# 09_TFCARD_USB2_0.net
KiCad netlist of a schematic drawn in Altium Designer
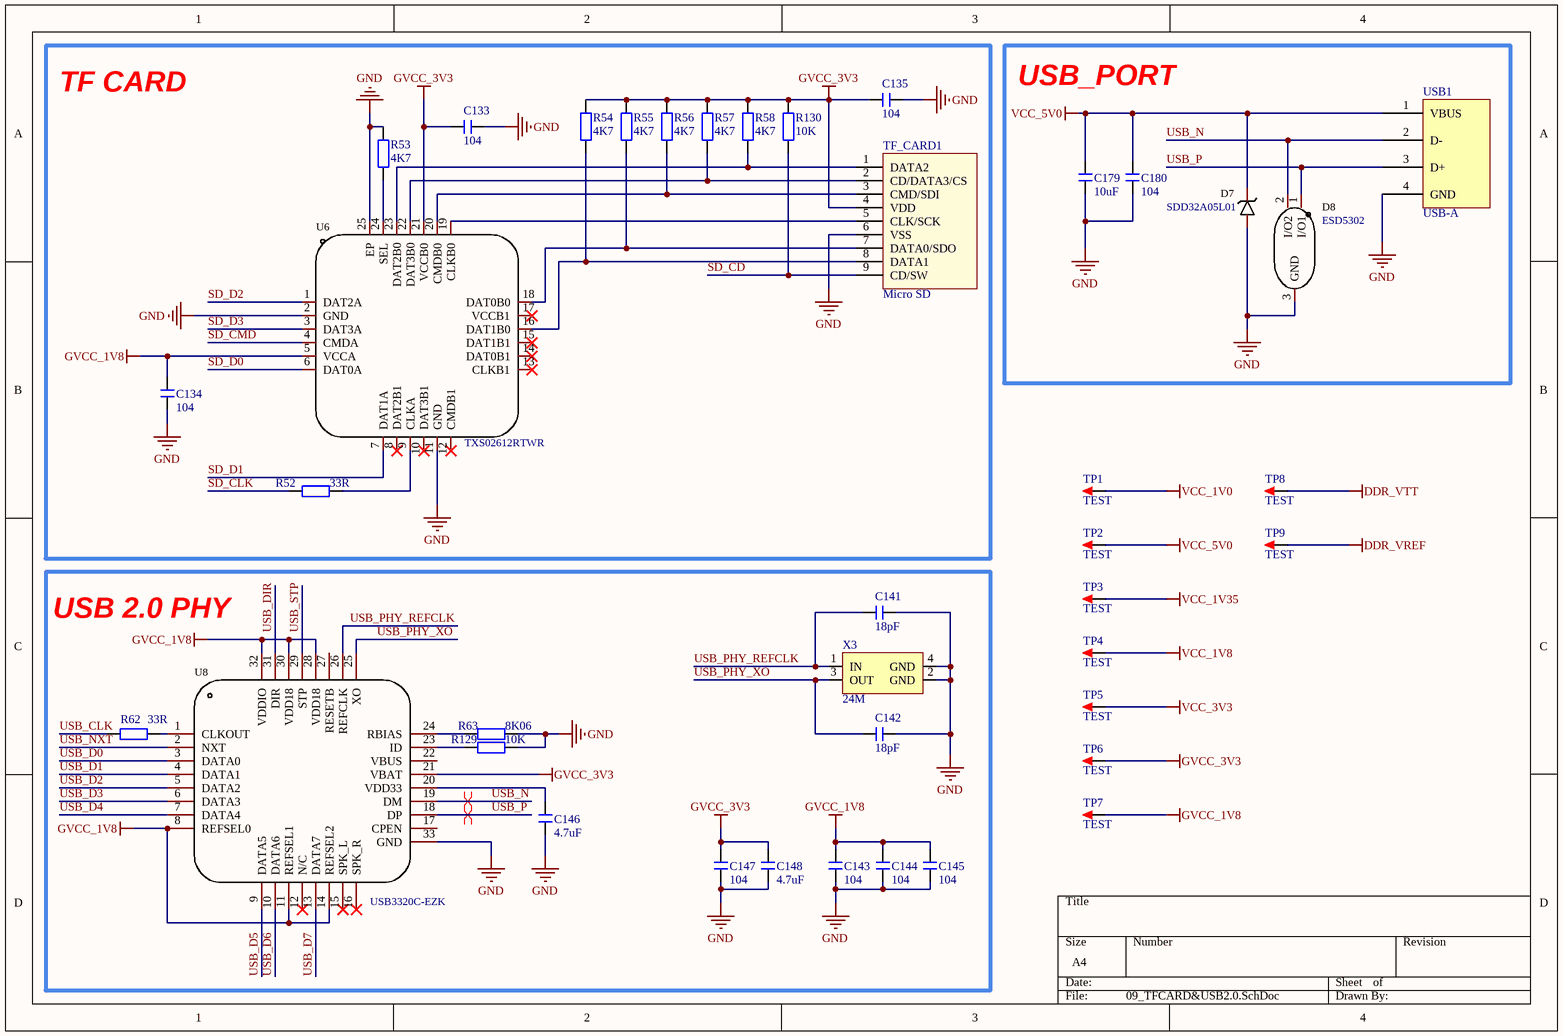
[diagram p0: 09_TFCARD&USB2.0.SchDoc]

(export (version "E")
  (design (tool "Eeschema 10.0.6"))
  (components
    (comp (ref "C133")
      (value "104")
      (footprint "C 0603")
      (description "无极性贴片电容")
      (fields (field (name "版权归属") "源创客"))
      (libsource (lib "STM32MP15x底板封装库V1.4") (part "C"))
    )
    (comp (ref "C134")
      (value "104")
      (footprint "C 0603")
      (description "无极性贴片电容")
      (fields (field (name "版权归属") "源创客"))
      (libsource (lib "STM32MP15x底板封装库V1.4") (part "C"))
    )
    (comp (ref "C135")
      (value "104")
      (footprint "C 0603")
      (description "无极性贴片电容")
      (fields (field (name "版权归属") "源创客"))
      (libsource (lib "STM32MP15x底板封装库V1.4") (part "C"))
    )
    (comp (ref "C141")
      (value "18pF")
      (footprint "C 0603")
      (description "无极性贴片电容")
      (fields (field (name "版权归属") "源创客"))
      (libsource (lib "STM32MP15x底板封装库V1.4") (part "C"))
    )
    (comp (ref "C142")
      (value "18pF")
      (footprint "C 0603")
      (description "无极性贴片电容")
      (fields (field (name "版权归属") "源创客"))
      (libsource (lib "STM32MP15x底板封装库V1.4") (part "C"))
    )
    (comp (ref "C143")
      (value "104")
      (footprint "C 0603")
      (description "无极性贴片电容")
      (fields (field (name "版权归属") "源创客"))
      (libsource (lib "STM32MP15x底板封装库V1.4") (part "C"))
    )
    (comp (ref "C144")
      (value "104")
      (footprint "C 0603")
      (description "无极性贴片电容")
      (fields (field (name "版权归属") "源创客"))
      (libsource (lib "STM32MP15x底板封装库V1.4") (part "C"))
    )
    (comp (ref "C145")
      (value "104")
      (footprint "C 0603")
      (description "无极性贴片电容")
      (fields (field (name "版权归属") "源创客"))
      (libsource (lib "STM32MP15x底板封装库V1.4") (part "C"))
    )
    (comp (ref "C146")
      (value "4.7uF")
      (footprint "C 0603")
      (description "无极性贴片电容")
      (fields (field (name "版权归属") "源创客"))
      (libsource (lib "STM32MP15x底板封装库V1.4") (part "C"))
    )
    (comp (ref "C147")
      (value "104")
      (footprint "C 0603")
      (description "无极性贴片电容")
      (fields (field (name "版权归属") "源创客"))
      (libsource (lib "STM32MP15x底板封装库V1.4") (part "C"))
    )
    (comp (ref "C148")
      (value "4.7uF")
      (footprint "C 0603")
      (description "无极性贴片电容")
      (fields (field (name "版权归属") "源创客"))
      (libsource (lib "STM32MP15x底板封装库V1.4") (part "C"))
    )
    (comp (ref "C179")
      (value "10uF")
      (footprint "C 0805")
      (description "无极性贴片电容")
      (fields (field (name "版权归属") "源创客"))
      (libsource (lib "STM32MP15x底板封装库V1.4") (part "C"))
    )
    (comp (ref "C180")
      (value "104")
      (footprint "C 0603")
      (description "无极性贴片电容")
      (fields (field (name "版权归属") "源创客"))
      (libsource (lib "STM32MP15x底板封装库V1.4") (part "C"))
    )
    (comp (ref "D7")
      (value "SDD32A05L01")
      (footprint "SOD-323")
      (fields (field (name "MANUFACTURER") "Brightking(君耀电子)"))
      (libsource (lib "SDD32A05L01") (part "SDD32A05L01"))
    )
    (comp (ref "D8")
      (value "ESD5302")
      (footprint "SOT23-3M")
      (fields (field (name "MANUFACTURER") "MSKSEMI(美森科)") (field (name "MANUFACTURER PART") "ESD5302F-MS"))
      (libsource (lib "ESD5302") (part "ESD5302"))
    )
    (comp (ref "R52")
      (value "33R")
      (footprint "R 0603")
      (description "贴片电阻")
      (fields (field (name "版权归属") "源创客"))
      (libsource (lib "STM32MP15x底板封装库V1.4") (part "R"))
    )
    (comp (ref "R53")
      (value "4K7")
      (footprint "R 0603")
      (description "贴片电阻")
      (fields (field (name "版权归属") "源创客"))
      (libsource (lib "STM32MP15x底板封装库V1.4") (part "R"))
    )
    (comp (ref "R54")
      (value "4K7")
      (footprint "R 0603")
      (description "贴片电阻")
      (fields (field (name "版权归属") "源创客"))
      (libsource (lib "STM32MP15x底板封装库V1.4") (part "R"))
    )
    (comp (ref "R55")
      (value "4K7")
      (footprint "R 0603")
      (description "贴片电阻")
      (fields (field (name "版权归属") "源创客"))
      (libsource (lib "STM32MP15x底板封装库V1.4") (part "R"))
    )
    (comp (ref "R56")
      (value "4K7")
      (footprint "R 0603")
      (description "贴片电阻")
      (fields (field (name "版权归属") "源创客"))
      (libsource (lib "STM32MP15x底板封装库V1.4") (part "R"))
    )
    (comp (ref "R57")
      (value "4K7")
      (footprint "R 0603")
      (description "贴片电阻")
      (fields (field (name "版权归属") "源创客"))
      (libsource (lib "STM32MP15x底板封装库V1.4") (part "R"))
    )
    (comp (ref "R58")
      (value "4K7")
      (footprint "R 0603")
      (description "贴片电阻")
      (fields (field (name "版权归属") "源创客"))
      (libsource (lib "STM32MP15x底板封装库V1.4") (part "R"))
    )
    (comp (ref "R62")
      (value "33R")
      (footprint "R 0603")
      (description "贴片电阻")
      (fields (field (name "版权归属") "源创客"))
      (libsource (lib "STM32MP15x底板封装库V1.4") (part "R"))
    )
    (comp (ref "R63")
      (value "8K06")
      (footprint "R 0603")
      (description "贴片电阻")
      (fields (field (name "版权归属") "源创客"))
      (libsource (lib "STM32MP15x底板封装库V1.4") (part "R"))
    )
    (comp (ref "R129")
      (value "10K")
      (footprint "R 0603")
      (description "贴片电阻")
      (fields (field (name "版权归属") "源创客"))
      (libsource (lib "STM32MP15x底板封装库V1.4") (part "R"))
    )
    (comp (ref "R130")
      (value "10K")
      (footprint "R 0603")
      (description "贴片电阻")
      (fields (field (name "版权归属") "源创客"))
      (libsource (lib "STM32MP15x底板封装库V1.4") (part "R"))
    )
    (comp (ref "TF_CARD1")
      (value "Micro SD")
      (footprint "Micro SD")
      (description "Micro SD卡")
      (fields (field (name "版权归属") "源创客"))
      (libsource (lib "STM32MP15x底板封装库V1.4") (part "Micro SD"))
    )
    (comp (ref "TP1")
      (value "TEST")
      (footprint "TEST 1")
      (description "测试点")
      (fields (field (name "版权归属") "源创客"))
      (libsource (lib "15.1 - 未分类器件") (part "TEST"))
    )
    (comp (ref "TP2")
      (value "TEST")
      (footprint "TEST 1")
      (description "测试点")
      (fields (field (name "版权归属") "源创客"))
      (libsource (lib "15.1 - 未分类器件") (part "TEST"))
    )
    (comp (ref "TP3")
      (value "TEST")
      (footprint "TEST 1")
      (description "测试点")
      (fields (field (name "版权归属") "源创客"))
      (libsource (lib "15.1 - 未分类器件") (part "TEST"))
    )
    (comp (ref "TP4")
      (value "TEST")
      (footprint "TEST 1")
      (description "测试点")
      (fields (field (name "版权归属") "源创客"))
      (libsource (lib "15.1 - 未分类器件") (part "TEST"))
    )
    (comp (ref "TP5")
      (value "TEST")
      (footprint "TEST 1")
      (description "测试点")
      (fields (field (name "版权归属") "源创客"))
      (libsource (lib "15.1 - 未分类器件") (part "TEST"))
    )
    (comp (ref "TP6")
      (value "TEST")
      (footprint "TEST 1")
      (description "测试点")
      (fields (field (name "版权归属") "源创客"))
      (libsource (lib "15.1 - 未分类器件") (part "TEST"))
    )
    (comp (ref "TP7")
      (value "TEST")
      (footprint "TEST 1")
      (description "测试点")
      (fields (field (name "版权归属") "源创客"))
      (libsource (lib "15.1 - 未分类器件") (part "TEST"))
    )
    (comp (ref "TP8")
      (value "TEST")
      (footprint "TEST 1")
      (description "测试点")
      (fields (field (name "版权归属") "源创客"))
      (libsource (lib "15.1 - 未分类器件") (part "TEST"))
    )
    (comp (ref "TP9")
      (value "TEST")
      (footprint "TEST 1")
      (description "测试点")
      (fields (field (name "版权归属") "源创客"))
      (libsource (lib "15.1 - 未分类器件") (part "TEST"))
    )
    (comp (ref "U6")
      (value "TXS02612RTWR")
      (footprint "QFN24 4x4_N")
      (fields (field (name "MANUFACTURER") "TI(德州仪器)"))
      (libsource (lib "TXS02612RTWR") (part "TXS02612RTWR"))
    )
    (comp (ref "U8")
      (value "USB3320C-EZK")
      (footprint "QFN32 5x5_L")
      (fields (field (name "MANUFACTURER") "MICROCHIP(美国微芯)"))
      (libsource (lib "USB3320C-EZK1") (part "USB3320C-EZK"))
    )
    (comp (ref "USB1") (value "USB-A") (footprint "USB-Short") (libsource (lib "Atom-N") (part "USB-A")))
    (comp (ref "X3")
      (value "24M")
      (footprint "XTAL-3225")
      (description "4脚无源晶振")
      (fields (field (name "版权归属") "源创客"))
      (libsource (lib "STM32MP15x底板封装库V1.4") (part "XTAL-4P"))
    )
  )
  (nets
    (net (code "1") (name "/SD_CD") (class "Default")
      (node (ref "R130") (pin "1") (pinfunction "1_1") (pintype "passive"))
      (node (ref "TF_CARD1") (pin "9") (pinfunction "CD/SW_9") (pintype "passive"))
    )
    (net (code "2") (name "/SD_CLK") (class "Default")
      (node (ref "R52") (pin "1") (pinfunction "1_1") (pintype "passive"))
    )
    (net (code "3") (name "/SD_CMD") (class "Default")
      (node (ref "U6") (pin "4") (pinfunction "CMDA_4") (pintype "passive"))
    )
    (net (code "4") (name "/SD_D0") (class "Default")
      (node (ref "U6") (pin "6") (pinfunction "DAT0A_6") (pintype "passive"))
    )
    (net (code "5") (name "/SD_D1") (class "Default")
      (node (ref "U6") (pin "7") (pinfunction "DAT1A_7") (pintype "passive"))
    )
    (net (code "6") (name "/SD_D2") (class "Default")
      (node (ref "U6") (pin "1") (pinfunction "DAT2A_1") (pintype "passive"))
    )
    (net (code "7") (name "/SD_D3") (class "Default")
      (node (ref "U6") (pin "3") (pinfunction "DAT3A_3") (pintype "passive"))
    )
    (net (code "8") (name "/USB_CLK") (class "Default")
      (node (ref "R62") (pin "2") (pinfunction "2_2") (pintype "passive"))
    )
    (net (code "9") (name "/USB_D0") (class "Default")
      (node (ref "U8") (pin "3") (pinfunction "DATA0_3") (pintype "passive"))
    )
    (net (code "10") (name "/USB_D1") (class "Default")
      (node (ref "U8") (pin "4") (pinfunction "DATA1_4") (pintype "passive"))
    )
    (net (code "11") (name "/USB_D2") (class "Default")
      (node (ref "U8") (pin "5") (pinfunction "DATA2_5") (pintype "passive"))
    )
    (net (code "12") (name "/USB_D3") (class "Default")
      (node (ref "U8") (pin "6") (pinfunction "DATA3_6") (pintype "passive"))
    )
    (net (code "13") (name "/USB_D4") (class "Default")
      (node (ref "U8") (pin "7") (pinfunction "DATA4_7") (pintype "passive"))
    )
    (net (code "14") (name "/USB_D5") (class "Default")
      (node (ref "U8") (pin "9") (pinfunction "DATA5_9") (pintype "passive"))
    )
    (net (code "15") (name "/USB_D6") (class "Default")
      (node (ref "U8") (pin "10") (pinfunction "DATA6_10") (pintype "passive"))
    )
    (net (code "16") (name "/USB_D7") (class "Default")
      (node (ref "U8") (pin "13") (pinfunction "DATA7_13") (pintype "passive"))
    )
    (net (code "17") (name "/USB_DIR") (class "Default")
      (node (ref "U8") (pin "31") (pinfunction "DIR_31") (pintype "passive"))
    )
    (net (code "18") (name "/USB_N") (class "Default")
      (node (ref "D8") (pin "2") (pinfunction "I/O2_2") (pintype "passive"))
      (node (ref "U8") (pin "19") (pinfunction "DM_19") (pintype "passive"))
      (node (ref "USB1") (pin "2") (pinfunction "D-_2") (pintype "passive"))
    )
    (net (code "19") (name "/USB_NXT") (class "Default")
      (node (ref "U8") (pin "2") (pinfunction "NXT_2") (pintype "passive"))
    )
    (net (code "20") (name "/USB_P") (class "Default")
      (node (ref "D8") (pin "1") (pinfunction "I/O1_1") (pintype "passive"))
      (node (ref "U8") (pin "18") (pinfunction "DP_18") (pintype "passive"))
      (node (ref "USB1") (pin "3") (pinfunction "D+_3") (pintype "passive"))
    )
    (net (code "21") (name "/USB_PHY_REFCLK") (class "Default")
      (node (ref "C141") (pin "2") (pinfunction "2_2") (pintype "passive"))
      (node (ref "U8") (pin "26") (pinfunction "REFCLK_26") (pintype "passive"))
      (node (ref "X3") (pin "1") (pinfunction "IN_1") (pintype "passive"))
    )
    (net (code "22") (name "/USB_PHY_XO") (class "Default")
      (node (ref "C142") (pin "2") (pinfunction "2_2") (pintype "passive"))
      (node (ref "U8") (pin "25") (pinfunction "XO_25") (pintype "passive"))
      (node (ref "X3") (pin "3") (pinfunction "OUT_3") (pintype "passive"))
    )
    (net (code "23") (name "/USB_STP") (class "Default")
      (node (ref "U8") (pin "29") (pinfunction "STP_29") (pintype "passive"))
    )
    (net (code "24") (name "DDR_VREF") (class "Default")
      (node (ref "TP9") (pin "1") (pinfunction "1_1") (pintype "passive"))
    )
    (net (code "25") (name "DDR_VTT") (class "Default")
      (node (ref "TP8") (pin "1") (pinfunction "1_1") (pintype "passive"))
    )
    (net (code "26") (name "GND") (class "Default")
      (node (ref "C133") (pin "1") (pinfunction "1_1") (pintype "passive"))
      (node (ref "C134") (pin "1") (pinfunction "1_1") (pintype "passive"))
      (node (ref "C135") (pin "2") (pinfunction "2_2") (pintype "passive"))
      (node (ref "C141") (pin "1") (pinfunction "1_1") (pintype "passive"))
      (node (ref "C142") (pin "1") (pinfunction "1_1") (pintype "passive"))
      (node (ref "C143") (pin "1") (pinfunction "1_1") (pintype "passive"))
      (node (ref "C144") (pin "1") (pinfunction "1_1") (pintype "passive"))
      (node (ref "C145") (pin "1") (pinfunction "1_1") (pintype "passive"))
      (node (ref "C146") (pin "1") (pinfunction "1_1") (pintype "passive"))
      (node (ref "C147") (pin "1") (pinfunction "1_1") (pintype "passive"))
      (node (ref "C148") (pin "1") (pinfunction "1_1") (pintype "passive"))
      (node (ref "C179") (pin "1") (pinfunction "1_1") (pintype "passive"))
      (node (ref "C180") (pin "1") (pinfunction "1_1") (pintype "passive"))
      (node (ref "D7") (pin "2") (pinfunction "A_2") (pintype "passive"))
      (node (ref "D8") (pin "3") (pinfunction "GND_3") (pintype "passive"))
      (node (ref "R129") (pin "2") (pinfunction "2_2") (pintype "passive"))
      (node (ref "R53") (pin "2") (pinfunction "2_2") (pintype "passive"))
      (node (ref "R63") (pin "2") (pinfunction "2_2") (pintype "passive"))
      (node (ref "TF_CARD1") (pin "6") (pinfunction "VSS_6") (pintype "passive"))
      (node (ref "U6") (pin "11") (pinfunction "GND_11") (pintype "passive"))
      (node (ref "U6") (pin "2") (pinfunction "GND_2") (pintype "passive"))
      (node (ref "U6") (pin "25") (pinfunction "EP_25") (pintype "passive"))
      (node (ref "U8") (pin "33") (pinfunction "GND_33") (pintype "passive"))
      (node (ref "USB1") (pin "4") (pinfunction "GND_4") (pintype "passive"))
      (node (ref "X3") (pin "2") (pinfunction "GND_2") (pintype "passive"))
      (node (ref "X3") (pin "4") (pinfunction "GND_4") (pintype "passive"))
    )
    (net (code "27") (name "GVCC_1V8") (class "Default")
      (node (ref "C134") (pin "2") (pinfunction "2_2") (pintype "passive"))
      (node (ref "C143") (pin "2") (pinfunction "2_2") (pintype "passive"))
      (node (ref "C144") (pin "2") (pinfunction "2_2") (pintype "passive"))
      (node (ref "C145") (pin "2") (pinfunction "2_2") (pintype "passive"))
      (node (ref "TP7") (pin "1") (pinfunction "1_1") (pintype "passive"))
      (node (ref "U6") (pin "5") (pinfunction "VCCA_5") (pintype "passive"))
      (node (ref "U8") (pin "11") (pinfunction "REFSEL1_11") (pintype "passive"))
      (node (ref "U8") (pin "14") (pinfunction "REFSEL2_14") (pintype "passive"))
      (node (ref "U8") (pin "28") (pinfunction "VDD18_28") (pintype "passive"))
      (node (ref "U8") (pin "30") (pinfunction "VDD18_30") (pintype "passive"))
      (node (ref "U8") (pin "32") (pinfunction "VDDIO_32") (pintype "passive"))
      (node (ref "U8") (pin "8") (pinfunction "REFSEL0_8") (pintype "passive"))
    )
    (net (code "28") (name "GVCC_3V3") (class "Default")
      (node (ref "C133") (pin "2") (pinfunction "2_2") (pintype "passive"))
      (node (ref "C135") (pin "1") (pinfunction "1_1") (pintype "passive"))
      (node (ref "C147") (pin "2") (pinfunction "2_2") (pintype "passive"))
      (node (ref "C148") (pin "2") (pinfunction "2_2") (pintype "passive"))
      (node (ref "R130") (pin "2") (pinfunction "2_2") (pintype "passive"))
      (node (ref "R54") (pin "2") (pinfunction "2_2") (pintype "passive"))
      (node (ref "R55") (pin "2") (pinfunction "2_2") (pintype "passive"))
      (node (ref "R56") (pin "2") (pinfunction "2_2") (pintype "passive"))
      (node (ref "R57") (pin "2") (pinfunction "2_2") (pintype "passive"))
      (node (ref "R58") (pin "2") (pinfunction "2_2") (pintype "passive"))
      (node (ref "TF_CARD1") (pin "4") (pinfunction "VDD_4") (pintype "passive"))
      (node (ref "TP6") (pin "1") (pinfunction "1_1") (pintype "passive"))
      (node (ref "U6") (pin "21") (pinfunction "VCCB0_21") (pintype "passive"))
      (node (ref "U8") (pin "21") (pinfunction "VBAT_21") (pintype "passive"))
    )
    (net (code "29") (name "Net-(TF_CARD1-CD{slash}DATA3{slash}CS)") (class "Default")
      (node (ref "R57") (pin "1") (pinfunction "1_1") (pintype "passive"))
      (node (ref "TF_CARD1") (pin "2") (pinfunction "CD/DATA3/CS_2") (pintype "passive"))
      (node (ref "U6") (pin "22") (pinfunction "DAT3B0_22") (pintype "passive"))
    )
    (net (code "30") (name "Net-(TF_CARD1-CLK{slash}SCK)") (class "Default")
      (node (ref "TF_CARD1") (pin "5") (pinfunction "CLK/SCK_5") (pintype "passive"))
      (node (ref "U6") (pin "19") (pinfunction "CLKB0_19") (pintype "passive"))
    )
    (net (code "31") (name "Net-(TF_CARD1-CMD{slash}SDI)") (class "Default")
      (node (ref "R56") (pin "1") (pinfunction "1_1") (pintype "passive"))
      (node (ref "TF_CARD1") (pin "3") (pinfunction "CMD/SDI_3") (pintype "passive"))
      (node (ref "U6") (pin "20") (pinfunction "CMDB0_20") (pintype "passive"))
    )
    (net (code "32") (name "Net-(TF_CARD1-DATA0{slash}SDO)") (class "Default")
      (node (ref "R55") (pin "1") (pinfunction "1_1") (pintype "passive"))
      (node (ref "TF_CARD1") (pin "7") (pinfunction "DATA0/SDO_7") (pintype "passive"))
      (node (ref "U6") (pin "18") (pinfunction "DAT0B0_18") (pintype "passive"))
    )
    (net (code "33") (name "Net-(TF_CARD1-DATA1)") (class "Default")
      (node (ref "R54") (pin "1") (pinfunction "1_1") (pintype "passive"))
      (node (ref "TF_CARD1") (pin "8") (pinfunction "DATA1_8") (pintype "passive"))
      (node (ref "U6") (pin "16") (pinfunction "DAT1B0_16") (pintype "passive"))
    )
    (net (code "34") (name "Net-(TF_CARD1-DATA2)") (class "Default")
      (node (ref "R58") (pin "1") (pinfunction "1_1") (pintype "passive"))
      (node (ref "TF_CARD1") (pin "1") (pinfunction "DATA2_1") (pintype "passive"))
      (node (ref "U6") (pin "23") (pinfunction "DAT2B0_23") (pintype "passive"))
    )
    (net (code "35") (name "Net-(U6-CLKA)") (class "Default")
      (node (ref "R52") (pin "2") (pinfunction "2_2") (pintype "passive"))
      (node (ref "U6") (pin "9") (pinfunction "CLKA_9") (pintype "passive"))
    )
    (net (code "36") (name "Net-(U6-SEL)") (class "Default")
      (node (ref "R53") (pin "1") (pinfunction "1_1") (pintype "passive"))
      (node (ref "U6") (pin "24") (pinfunction "SEL_24") (pintype "passive"))
    )
    (net (code "37") (name "Net-(U8-CLKOUT)") (class "Default")
      (node (ref "R62") (pin "1") (pinfunction "1_1") (pintype "passive"))
      (node (ref "U8") (pin "1") (pinfunction "CLKOUT_1") (pintype "passive"))
    )
    (net (code "38") (name "Net-(U8-ID)") (class "Default")
      (node (ref "R129") (pin "1") (pinfunction "1_1") (pintype "passive"))
      (node (ref "U8") (pin "23") (pinfunction "ID_23") (pintype "passive"))
    )
    (net (code "39") (name "Net-(U8-RBIAS)") (class "Default")
      (node (ref "R63") (pin "1") (pinfunction "1_1") (pintype "passive"))
      (node (ref "U8") (pin "24") (pinfunction "RBIAS_24") (pintype "passive"))
    )
    (net (code "40") (name "Net-(U8-VDD33)") (class "Default")
      (node (ref "C146") (pin "2") (pinfunction "2_2") (pintype "passive"))
      (node (ref "U8") (pin "20") (pinfunction "VDD33_20") (pintype "passive"))
    )
    (net (code "41") (name "VCC_1V0") (class "Default")
      (node (ref "TP1") (pin "1") (pinfunction "1_1") (pintype "passive"))
    )
    (net (code "42") (name "VCC_1V8") (class "Default")
      (node (ref "TP4") (pin "1") (pinfunction "1_1") (pintype "passive"))
    )
    (net (code "43") (name "VCC_1V35") (class "Default")
      (node (ref "TP3") (pin "1") (pinfunction "1_1") (pintype "passive"))
    )
    (net (code "44") (name "VCC_3V3") (class "Default")
      (node (ref "TP5") (pin "1") (pinfunction "1_1") (pintype "passive"))
    )
    (net (code "45") (name "VCC_5V0") (class "Default")
      (node (ref "C179") (pin "2") (pinfunction "2_2") (pintype "passive"))
      (node (ref "C180") (pin "2") (pinfunction "2_2") (pintype "passive"))
      (node (ref "D7") (pin "1") (pinfunction "C_1") (pintype "passive"))
      (node (ref "TP2") (pin "1") (pinfunction "1_1") (pintype "passive"))
      (node (ref "USB1") (pin "1") (pinfunction "VBUS_1") (pintype "passive"))
    )
    (net (code "46") (name "unconnected-(U6-CLKB1-Pad13)") (class "Default")
      (node (ref "U6") (pin "13") (pinfunction "CLKB1_13") (pintype "passive+no_connect"))
    )
    (net (code "47") (name "unconnected-(U6-CMDB1-Pad12)") (class "Default")
      (node (ref "U6") (pin "12") (pinfunction "CMDB1_12") (pintype "passive+no_connect"))
    )
    (net (code "48") (name "unconnected-(U6-DAT0B1-Pad14)") (class "Default")
      (node (ref "U6") (pin "14") (pinfunction "DAT0B1_14") (pintype "passive+no_connect"))
    )
    (net (code "49") (name "unconnected-(U6-DAT1B1-Pad15)") (class "Default")
      (node (ref "U6") (pin "15") (pinfunction "DAT1B1_15") (pintype "passive+no_connect"))
    )
    (net (code "50") (name "unconnected-(U6-DAT2B1-Pad8)") (class "Default")
      (node (ref "U6") (pin "8") (pinfunction "DAT2B1_8") (pintype "passive+no_connect"))
    )
    (net (code "51") (name "unconnected-(U6-DAT3B1-Pad10)") (class "Default")
      (node (ref "U6") (pin "10") (pinfunction "DAT3B1_10") (pintype "passive+no_connect"))
    )
    (net (code "52") (name "unconnected-(U6-VCCB1-Pad17)") (class "Default")
      (node (ref "U6") (pin "17") (pinfunction "VCCB1_17") (pintype "passive+no_connect"))
    )
    (net (code "53") (name "unconnected-(U8-CPEN-Pad17)") (class "Default")
      (node (ref "U8") (pin "17") (pinfunction "CPEN_17") (pintype "passive"))
    )
    (net (code "54") (name "unconnected-(U8-N{slash}C-Pad12)") (class "Default")
      (node (ref "U8") (pin "12") (pinfunction "N/C_12") (pintype "passive+no_connect"))
    )
    (net (code "55") (name "unconnected-(U8-RESETB-Pad27)") (class "Default")
      (node (ref "U8") (pin "27") (pinfunction "RESETB_27") (pintype "passive"))
    )
    (net (code "56") (name "unconnected-(U8-SPK_L-Pad15)") (class "Default")
      (node (ref "U8") (pin "15") (pinfunction "SPK_L_15") (pintype "passive+no_connect"))
    )
    (net (code "57") (name "unconnected-(U8-SPK_R-Pad16)") (class "Default")
      (node (ref "U8") (pin "16") (pinfunction "SPK_R_16") (pintype "passive+no_connect"))
    )
    (net (code "58") (name "unconnected-(U8-VBUS-Pad22)") (class "Default")
      (node (ref "U8") (pin "22") (pinfunction "VBUS_22") (pintype "passive"))
    )
  )
)
